# pcb_reguladores.net
KiCad netlist of a schematic drawn in EAGLE
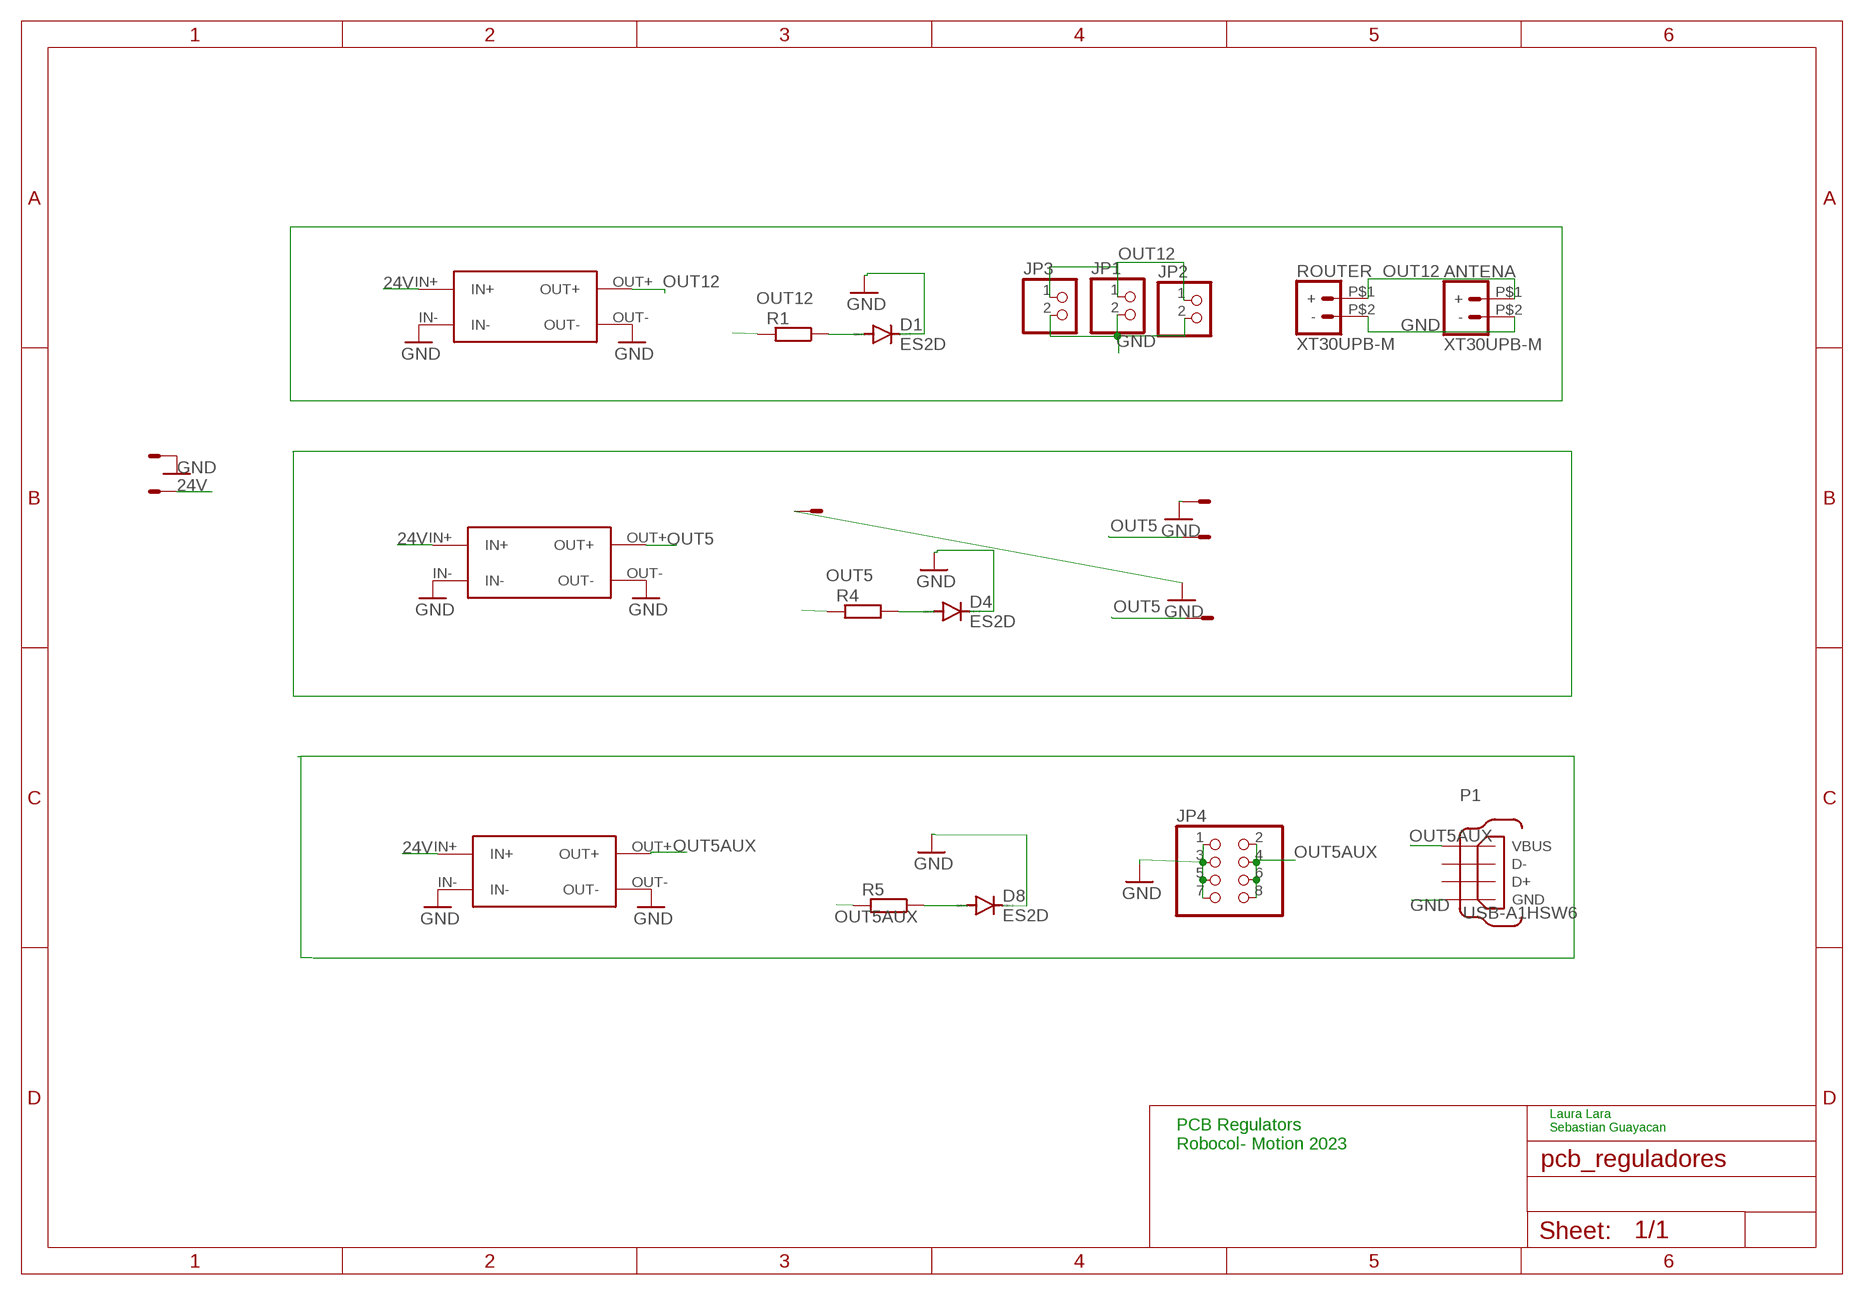
[diagram p0: schematic, sheet 1]

(export (version "E")
  (design (tool "Eeschema 10.0.6"))
  (components
    (comp (ref "ANTENA")
      (value "XT30UPB-M")
      (footprint "eagle-import:XT30UPB-M")
      (fields (field (name "MF") "amass"))
      (libsource (lib "eagle-import") (part "XT30UPB-M"))
    )
    (comp (ref "D1")
      (value "ES2D")
      (footprint "eagle-import:SMB")
      (libsource (lib "eagle-import") (part "ES2D"))
    )
    (comp (ref "D4")
      (value "ES2D")
      (footprint "eagle-import:SMB")
      (libsource (lib "eagle-import") (part "ES2D"))
    )
    (comp (ref "D8")
      (value "ES2D")
      (footprint "eagle-import:SMB")
      (libsource (lib "eagle-import") (part "ES2D"))
    )
    (comp (ref "JP1")
      (value "PINHD-1X2")
      (footprint "eagle-import:1X02")
      (libsource (lib "eagle-import") (part "PINHD-1X2"))
    )
    (comp (ref "JP2")
      (value "PINHD-1X2")
      (footprint "eagle-import:1X02")
      (libsource (lib "eagle-import") (part "PINHD-1X2"))
    )
    (comp (ref "JP3")
      (value "PINHD-1X2")
      (footprint "eagle-import:1X02")
      (libsource (lib "eagle-import") (part "PINHD-1X2"))
    )
    (comp (ref "JP4")
      (value "PINHD-2X4")
      (footprint "eagle-import:2X04")
      (libsource (lib "eagle-import") (part "PINHD-2X4"))
    )
    (comp (ref "P1")
      (value "USB-A1HSW6")
      (footprint "eagle-import:OST_USB-A1HSW6")
      (fields (field (name "MF") "On Shore"))
      (libsource (lib "eagle-import") (part "USB-A1HSW6"))
    )
    (comp (ref "R1")
      (value "SMK")
      (footprint "eagle-import:SMK")
      (libsource (lib "eagle-import") (part "SMK"))
    )
    (comp (ref "R4")
      (value "SMK")
      (footprint "eagle-import:SMK")
      (libsource (lib "eagle-import") (part "SMK"))
    )
    (comp (ref "R5")
      (value "SMK")
      (footprint "eagle-import:SMK")
      (libsource (lib "eagle-import") (part "SMK"))
    )
    (comp (ref "REG5AUX")
      (value "XL4015_5A")
      (footprint "eagle-import:XL4015_PADS")
      (libsource (lib "eagle-import") (part "XL4015_5A"))
    )
    (comp (ref "REG5V")
      (value "XL4015_5A")
      (footprint "eagle-import:XL4015_PADS")
      (libsource (lib "eagle-import") (part "XL4015_5A"))
    )
    (comp (ref "REG12V")
      (value "XL4015_5A")
      (footprint "eagle-import:XL4015_PADS")
      (libsource (lib "eagle-import") (part "XL4015_5A"))
    )
    (comp (ref "ROUTER")
      (value "XT30UPB-M")
      (footprint "eagle-import:XT30UPB-M")
      (fields (field (name "MF") "amass"))
      (libsource (lib "eagle-import") (part "XT30UPB-M"))
    )
    (comp (ref "V_IN")
      (value "5566-25569-2")
      (footprint "eagle-import:5569-2")
      (libsource (lib "eagle-import") (part "5566-25569-2"))
    )
    (comp (ref "X1")
      (value "5566-25569-2")
      (footprint "eagle-import:5569-2")
      (libsource (lib "eagle-import") (part "5566-25569-2"))
    )
    (comp (ref "X3")
      (value "5566-25569-2")
      (footprint "eagle-import:5569-2")
      (libsource (lib "eagle-import") (part "5566-25569-2"))
    )
  )
  (nets
    (net (code "1") (name "/24V") (class "Default")
      (node (ref "REG12V") (pin "IN+") (pinfunction "IN+_IN+") (pintype "bidirectional"))
      (node (ref "REG5AUX") (pin "IN+") (pinfunction "IN+_IN+") (pintype "bidirectional"))
      (node (ref "REG5V") (pin "IN+") (pinfunction "IN+_IN+") (pintype "bidirectional"))
      (node (ref "V_IN") (pin "2") (pinfunction "S_2") (pintype "passive"))
    )
    (net (code "2") (name "/OUT5") (class "Default")
      (node (ref "R4") (pin "2") (pinfunction "2_2") (pintype "passive"))
      (node (ref "REG5V") (pin "OUT+") (pinfunction "OUT+_OUT+") (pintype "bidirectional"))
      (node (ref "X1") (pin "2") (pinfunction "S_2") (pintype "passive"))
      (node (ref "X3") (pin "2") (pinfunction "S_2") (pintype "passive"))
    )
    (net (code "3") (name "/OUT5AUX") (class "Default")
      (node (ref "JP4") (pin "2") (pinfunction "2_2") (pintype "passive"))
      (node (ref "JP4") (pin "4") (pinfunction "4_4") (pintype "passive"))
      (node (ref "JP4") (pin "6") (pinfunction "6_6") (pintype "passive"))
      (node (ref "JP4") (pin "8") (pinfunction "8_8") (pintype "passive"))
      (node (ref "P1") (pin "1") (pinfunction "VBUS_1") (pintype "power_in"))
      (node (ref "R5") (pin "2") (pinfunction "2_2") (pintype "passive"))
      (node (ref "REG5AUX") (pin "OUT+") (pinfunction "OUT+_OUT+") (pintype "bidirectional"))
    )
    (net (code "4") (name "/OUT12") (class "Default")
      (node (ref "ANTENA") (pin "P$1") (pinfunction "+_P$1") (pintype "passive"))
      (node (ref "JP1") (pin "1") (pinfunction "1_1") (pintype "passive"))
      (node (ref "JP2") (pin "1") (pinfunction "1_1") (pintype "passive"))
      (node (ref "JP3") (pin "1") (pinfunction "1_1") (pintype "passive"))
      (node (ref "R1") (pin "2") (pinfunction "2_2") (pintype "passive"))
      (node (ref "REG12V") (pin "OUT+") (pinfunction "OUT+_OUT+") (pintype "bidirectional"))
      (node (ref "ROUTER") (pin "P$1") (pinfunction "+_P$1") (pintype "passive"))
    )
    (net (code "5") (name "GND") (class "Default")
      (node (ref "ANTENA") (pin "P$2") (pinfunction "-_P$2") (pintype "passive"))
      (node (ref "D1") (pin "C") (pinfunction "C_C") (pintype "passive"))
      (node (ref "D4") (pin "C") (pinfunction "C_C") (pintype "passive"))
      (node (ref "D8") (pin "C") (pinfunction "C_C") (pintype "passive"))
      (node (ref "JP4") (pin "1") (pinfunction "1_1") (pintype "passive"))
      (node (ref "JP4") (pin "3") (pinfunction "3_3") (pintype "passive"))
      (node (ref "JP4") (pin "5") (pinfunction "5_5") (pintype "passive"))
      (node (ref "JP4") (pin "7") (pinfunction "7_7") (pintype "passive"))
      (node (ref "P1") (pin "4") (pinfunction "GND_4") (pintype "power_in"))
      (node (ref "REG12V") (pin "IN-") (pinfunction "IN-_IN-") (pintype "bidirectional"))
      (node (ref "REG12V") (pin "OUT-") (pinfunction "OUT-_OUT-") (pintype "bidirectional"))
      (node (ref "REG5AUX") (pin "IN-") (pinfunction "IN-_IN-") (pintype "bidirectional"))
      (node (ref "REG5AUX") (pin "OUT-") (pinfunction "OUT-_OUT-") (pintype "bidirectional"))
      (node (ref "REG5V") (pin "IN-") (pinfunction "IN-_IN-") (pintype "bidirectional"))
      (node (ref "REG5V") (pin "OUT-") (pinfunction "OUT-_OUT-") (pintype "bidirectional"))
      (node (ref "ROUTER") (pin "P$2") (pinfunction "-_P$2") (pintype "passive"))
      (node (ref "V_IN") (pin "1") (pinfunction "S_1") (pintype "passive"))
      (node (ref "X1") (pin "1") (pinfunction "S_1") (pintype "passive"))
      (node (ref "X3") (pin "1") (pinfunction "S_1") (pintype "passive"))
    )
    (net (code "6") (name "Net-(D1-PadA)") (class "Default")
      (node (ref "D1") (pin "A") (pinfunction "A_A") (pintype "passive"))
      (node (ref "R1") (pin "1") (pinfunction "1_1") (pintype "passive"))
    )
    (net (code "7") (name "Net-(D4-PadA)") (class "Default")
      (node (ref "D4") (pin "A") (pinfunction "A_A") (pintype "passive"))
      (node (ref "R4") (pin "1") (pinfunction "1_1") (pintype "passive"))
    )
    (net (code "8") (name "Net-(D8-PadA)") (class "Default")
      (node (ref "D8") (pin "A") (pinfunction "A_A") (pintype "passive"))
      (node (ref "R5") (pin "1") (pinfunction "1_1") (pintype "passive"))
    )
    (net (code "9") (name "Net-(JP1-Pad2)") (class "Default")
      (node (ref "JP1") (pin "2") (pinfunction "2_2") (pintype "passive"))
      (node (ref "JP2") (pin "2") (pinfunction "2_2") (pintype "passive"))
      (node (ref "JP3") (pin "2") (pinfunction "2_2") (pintype "passive"))
    )
    (net (code "10") (name "unconnected-(P1-D+-Pad3)") (class "Default")
      (node (ref "P1") (pin "3") (pinfunction "D+_3") (pintype "bidirectional"))
    )
    (net (code "11") (name "unconnected-(P1-D--Pad2)") (class "Default")
      (node (ref "P1") (pin "2") (pinfunction "D-_2") (pintype "bidirectional"))
    )
  )
)
